# Sensor_IO_Buttons_LED.net
KiCad netlist of a schematic drawn in Altium Designer
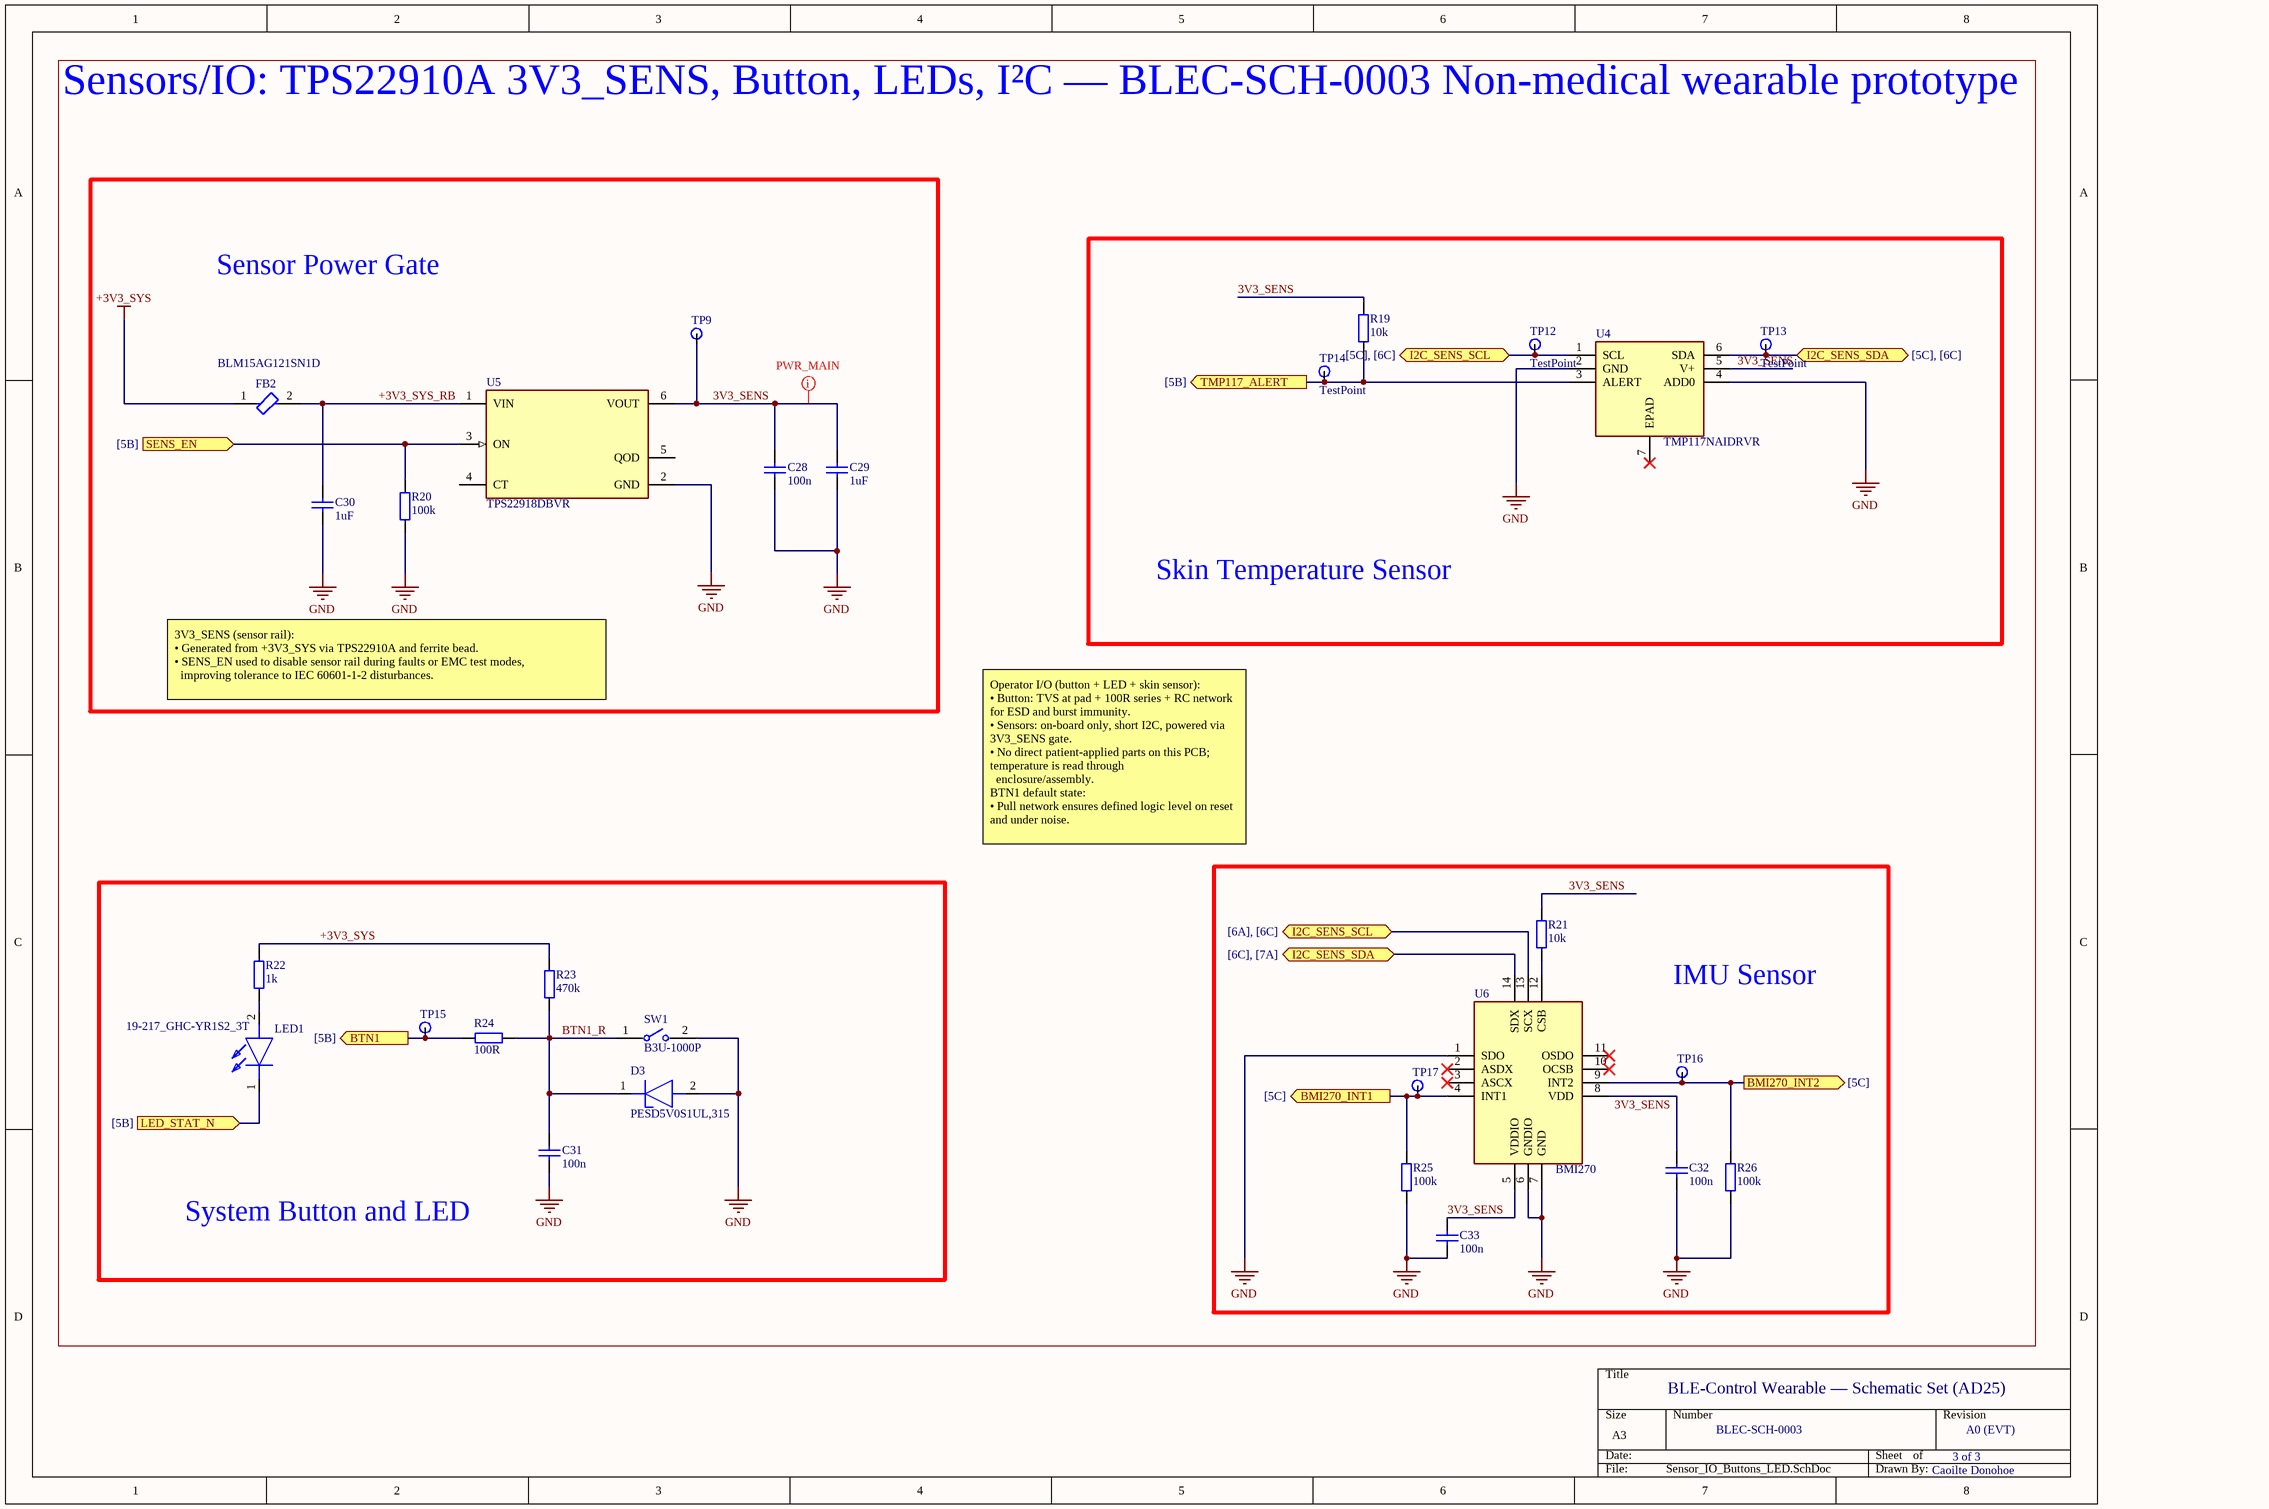
[diagram p0: Sensor_IO_Buttons_LED.SchDoc]

(export (version "E")
  (design (tool "Eeschema 10.0.6"))
  (components
    (comp (ref "C28")
      (value "100n")
      (footprint "CAP_0402")
      (description "Ceramic Chip Capacitor 0402")
      (fields (field (name "VOLTAGE") "10V") (field (name "TOLERANCE") "10%"))
      (libsource (lib "BLE-Control") (part "C_0402"))
    )
    (comp (ref "C29")
      (value "1uF")
      (footprint "CAP_0402")
      (description "Ceramic Chip Capacitor 0402")
      (fields (field (name "VOLTAGE") "10V") (field (name "TOLERANCE") "10%"))
      (libsource (lib "BLE-Control") (part "C_0402"))
    )
    (comp (ref "C30")
      (value "1uF")
      (footprint "CAP_0402")
      (description "Ceramic Chip Capacitor 0402")
      (fields (field (name "VOLTAGE") "10V") (field (name "TOLERANCE") "10%"))
      (libsource (lib "BLE-Control") (part "C_0402"))
    )
    (comp (ref "C31")
      (value "100n")
      (footprint "CAP_0402")
      (description "Ceramic Chip Capacitor 0402")
      (fields (field (name "VOLTAGE") "10V") (field (name "TOLERANCE") "10%"))
      (libsource (lib "BLE-Control") (part "C_0402"))
    )
    (comp (ref "C32")
      (value "100n")
      (footprint "CAP_0402")
      (description "Ceramic Chip Capacitor 0402")
      (fields (field (name "VOLTAGE") "10V") (field (name "TOLERANCE") "10%"))
      (libsource (lib "BLE-Control") (part "C_0402"))
    )
    (comp (ref "C33")
      (value "100n")
      (footprint "CAP_0402")
      (description "Ceramic Chip Capacitor 0402")
      (fields (field (name "VOLTAGE") "10V") (field (name "TOLERANCE") "10%"))
      (libsource (lib "BLE-Control") (part "C_0402"))
    )
    (comp (ref "D3")
      (value "PESD5V0S1UL,315")
      (footprint "SamacSys:PESD5V0S1BL315")
      (description "Diode ESD (Uni-directional)")
      (fields (field (name "MOUSER PART NUMBER") "771-PESD5V0S1UL315"))
      (libsource (lib "BLE-Control") (part "PESD5V0S1UL,315"))
    )
    (comp (ref "FB2")
      (value "BLM15AG121SN1D")
      (footprint "FP-BLM15-0_05-IPC_A")
      (description "Chip Ferrite Bead, 0402, 120Ω @ 100MHz, 0.19Ω, 25%, 550mA")
      (fields (field (name "TOLERANCE") "25%"))
      (libsource (lib "BLE-Control") (part "CMP-0686-00170-4"))
    )
    (comp (ref "LED1")
      (value "19-217_GHC-YR1S2_3T")
      (footprint "SamacSys:LEDC1608X50N")
      (description "LED")
      (fields
        (field (name "MANUFACTURER_PART_NUMBER") "19-217/GHC-YR1S2/3T")
        (field (name "MOUSER PART NUMBER") "638-19217GHCYR1S23T")
      )
      (libsource (lib "BLE-Control") (part "19-217_GHC-YR1S2_3T"))
    )
    (comp (ref "R19")
      (value "10k")
      (footprint "RES_0402")
      (description "Resistor SMD 0402")
      (libsource (lib "BLE-Control") (part "R_0402"))
    )
    (comp (ref "R20")
      (value "100k")
      (footprint "BLE-Control:RES_0402")
      (description "Resistor SMD 0402")
      (libsource (lib "BLE-Control") (part "R_0402"))
    )
    (comp (ref "R21")
      (value "10k")
      (footprint "RES_0402")
      (description "Resistor SMD 0402")
      (libsource (lib "BLE-Control") (part "R_0402"))
    )
    (comp (ref "R22")
      (value "1k")
      (footprint "RES_0402")
      (description "Resistor SMD 0402")
      (libsource (lib "BLE-Control") (part "R_0402"))
    )
    (comp (ref "R23")
      (value "470k")
      (footprint "RES_0402")
      (description "Resistor SMD 0402")
      (libsource (lib "BLE-Control") (part "R_0402"))
    )
    (comp (ref "R24")
      (value "100R")
      (footprint "RES_0402")
      (description "Resistor SMD 0402")
      (libsource (lib "BLE-Control") (part "R_0402"))
    )
    (comp (ref "R25")
      (value "100k")
      (footprint "RES_0402")
      (description "Resistor SMD 0402")
      (libsource (lib "BLE-Control") (part "R_0402"))
    )
    (comp (ref "R26")
      (value "100k")
      (footprint "RES_0402")
      (description "Resistor SMD 0402")
      (libsource (lib "BLE-Control") (part "R_0402"))
    )
    (comp (ref "SW1")
      (value "B3U-1000P")
      (footprint "FP-B3U-1000P-MFG")
      (description "SWITCH TACTILE SPST-NO 0.05A 12V")
      (libsource (lib "BLE-Control") (part "Omron B3U-1000P_Switch"))
    )
    (comp (ref "TP9")
      (value "~")
      (footprint "TP_VIA_0p75")
      (libsource (lib "BLE-Control") (part "TestPoint"))
    )
    (comp (ref "TP12")
      (value "TestPoint")
      (footprint "TP_VIA_0p75")
      (libsource (lib "BLE-Control") (part "TestPoint"))
    )
    (comp (ref "TP13")
      (value "TestPoint")
      (footprint "TP_VIA_0p75")
      (libsource (lib "BLE-Control") (part "TestPoint"))
    )
    (comp (ref "TP14")
      (value "TestPoint")
      (footprint "TP_VIA_0p75")
      (libsource (lib "BLE-Control") (part "TestPoint"))
    )
    (comp (ref "TP15")
      (value "~")
      (footprint "TP_VIA_0p75")
      (libsource (lib "BLE-Control") (part "TestPoint"))
    )
    (comp (ref "TP16")
      (value "~")
      (footprint "TP_VIA_0p75")
      (libsource (lib "BLE-Control") (part "TestPoint"))
    )
    (comp (ref "TP17")
      (value "~")
      (footprint "TP_VIA_0p75")
      (libsource (lib "BLE-Control") (part "TestPoint"))
    )
    (comp (ref "U4")
      (value "TMP117NAIDRVR")
      (footprint "SON65P200X200X80-7N")
      (description "Integrated Circuit")
      (fields (field (name "MOUSER PART NUMBER") "595-TMP117NAIDRVR"))
      (libsource (lib "*") (part "TMP117NAIDRVR"))
    )
    (comp (ref "U5")
      (value "TPS22918DBVR")
      (footprint "FP-DBV0006A-IPC_B")
      (description "IC SINGLE CHANNEL LOAD SWITCH")
      (libsource (lib "BLE-Control") (part "TPS22918DBVR"))
    )
    (comp (ref "U6")
      (value "BMI270")
      (footprint "BMI270")
      (description "Integrated Circuit")
      (fields (field (name "MOUSER PART NUMBER") "262-BMI270"))
      (libsource (lib "*") (part "BMI270"))
    )
  )
  (nets
    (net (code "1") (name "+3V3_SYS") (class "Default")
      (node (ref "FB2") (pin "1") (pinfunction "1_1") (pintype "passive"))
      (node (ref "R22") (pin "2") (pinfunction "2_2") (pintype "passive"))
      (node (ref "R23") (pin "2") (pinfunction "2_2") (pintype "passive"))
    )
    (net (code "2") (name "/+3V3_SYS_RB") (class "Default")
      (node (ref "C30") (pin "2") (pinfunction "2_2") (pintype "passive"))
      (node (ref "FB2") (pin "2") (pinfunction "2_2") (pintype "passive"))
      (node (ref "U5") (pin "1") (pinfunction "VIN_1") (pintype "power_in"))
    )
    (net (code "3") (name "/3V3_SENS") (class "Default")
      (node (ref "C28") (pin "2") (pinfunction "2_2") (pintype "passive"))
      (node (ref "C29") (pin "2") (pinfunction "2_2") (pintype "passive"))
      (node (ref "C32") (pin "2") (pinfunction "2_2") (pintype "passive"))
      (node (ref "C33") (pin "2") (pinfunction "2_2") (pintype "passive"))
      (node (ref "R19") (pin "2") (pinfunction "2_2") (pintype "passive"))
      (node (ref "R21") (pin "2") (pinfunction "2_2") (pintype "passive"))
      (node (ref "TP9") (pin "1") (pinfunction "0_1") (pintype "passive"))
      (node (ref "U4") (pin "5") (pinfunction "V+_5") (pintype "passive"))
      (node (ref "U5") (pin "6") (pinfunction "VOUT_6") (pintype "passive"))
      (node (ref "U6") (pin "5") (pinfunction "VDDIO_5") (pintype "passive"))
      (node (ref "U6") (pin "8") (pinfunction "VDD_8") (pintype "passive"))
    )
    (net (code "4") (name "/BMI270_INT1") (class "Default")
      (node (ref "R25") (pin "2") (pinfunction "2_2") (pintype "passive"))
      (node (ref "TP17") (pin "1") (pinfunction "0_1") (pintype "passive"))
      (node (ref "U6") (pin "4") (pinfunction "INT1_4") (pintype "passive"))
    )
    (net (code "5") (name "/BMI270_INT2") (class "Default")
      (node (ref "R26") (pin "2") (pinfunction "2_2") (pintype "passive"))
      (node (ref "TP16") (pin "1") (pinfunction "0_1") (pintype "passive"))
      (node (ref "U6") (pin "9") (pinfunction "INT2_9") (pintype "passive"))
    )
    (net (code "6") (name "/BTN1") (class "Default")
      (node (ref "R24") (pin "2") (pinfunction "2_2") (pintype "passive"))
      (node (ref "TP15") (pin "1") (pinfunction "0_1") (pintype "passive"))
    )
    (net (code "7") (name "/BTN1_R") (class "Default")
      (node (ref "C31") (pin "2") (pinfunction "2_2") (pintype "passive"))
      (node (ref "D3") (pin "1") (pinfunction "K_1") (pintype "passive"))
      (node (ref "R23") (pin "1") (pinfunction "1_1") (pintype "passive"))
      (node (ref "R24") (pin "1") (pinfunction "1_1") (pintype "passive"))
      (node (ref "SW1") (pin "1") (pinfunction "1_1") (pintype "passive"))
    )
    (net (code "8") (name "/I2C_SENS_SCL") (class "Default")
      (node (ref "TP12") (pin "1") (pinfunction "0_1") (pintype "passive"))
      (node (ref "U4") (pin "1") (pinfunction "SCL_1") (pintype "passive"))
      (node (ref "U6") (pin "13") (pinfunction "SCX_13") (pintype "passive"))
    )
    (net (code "9") (name "/I2C_SENS_SDA") (class "Default")
      (node (ref "TP13") (pin "1") (pinfunction "0_1") (pintype "passive"))
      (node (ref "U4") (pin "6") (pinfunction "SDA_6") (pintype "passive"))
      (node (ref "U6") (pin "14") (pinfunction "SDX_14") (pintype "passive"))
    )
    (net (code "10") (name "/LED_STAT_N") (class "Default")
      (node (ref "LED1") (pin "1") (pinfunction "K_1") (pintype "passive"))
    )
    (net (code "11") (name "/SENS_EN") (class "Default")
      (node (ref "R20") (pin "2") (pinfunction "2_2") (pintype "passive"))
      (node (ref "U5") (pin "3") (pinfunction "ON_3") (pintype "input"))
    )
    (net (code "12") (name "/TMP117_ALERT") (class "Default")
      (node (ref "R19") (pin "1") (pinfunction "1_1") (pintype "passive"))
      (node (ref "TP14") (pin "1") (pinfunction "0_1") (pintype "passive"))
      (node (ref "U4") (pin "3") (pinfunction "ALERT_3") (pintype "passive"))
    )
    (net (code "13") (name "GND") (class "Default")
      (node (ref "C28") (pin "1") (pinfunction "1_1") (pintype "passive"))
      (node (ref "C29") (pin "1") (pinfunction "1_1") (pintype "passive"))
      (node (ref "C30") (pin "1") (pinfunction "1_1") (pintype "passive"))
      (node (ref "C31") (pin "1") (pinfunction "1_1") (pintype "passive"))
      (node (ref "C32") (pin "1") (pinfunction "1_1") (pintype "passive"))
      (node (ref "C33") (pin "1") (pinfunction "1_1") (pintype "passive"))
      (node (ref "D3") (pin "2") (pinfunction "A_2") (pintype "passive"))
      (node (ref "R20") (pin "1") (pinfunction "1_1") (pintype "passive"))
      (node (ref "R25") (pin "1") (pinfunction "1_1") (pintype "passive"))
      (node (ref "R26") (pin "1") (pinfunction "1_1") (pintype "passive"))
      (node (ref "SW1") (pin "2") (pinfunction "2_2") (pintype "passive"))
      (node (ref "U4") (pin "2") (pinfunction "GND_2") (pintype "passive"))
      (node (ref "U4") (pin "4") (pinfunction "ADD0_4") (pintype "passive"))
      (node (ref "U5") (pin "2") (pinfunction "GND_2") (pintype "power_in"))
      (node (ref "U6") (pin "1") (pinfunction "SDO_1") (pintype "passive"))
      (node (ref "U6") (pin "6") (pinfunction "GNDIO_6") (pintype "passive"))
      (node (ref "U6") (pin "7") (pinfunction "GND_7") (pintype "passive"))
    )
    (net (code "14") (name "Net-(LED1-A)") (class "Default")
      (node (ref "LED1") (pin "2") (pinfunction "A_2") (pintype "passive"))
      (node (ref "R22") (pin "1") (pinfunction "1_1") (pintype "passive"))
    )
    (net (code "15") (name "Net-(U6-CSB)") (class "Default")
      (node (ref "R21") (pin "1") (pinfunction "1_1") (pintype "passive"))
      (node (ref "U6") (pin "12") (pinfunction "CSB_12") (pintype "passive"))
    )
    (net (code "16") (name "unconnected-(U4-EPAD-Pad7)") (class "Default")
      (node (ref "U4") (pin "7") (pinfunction "EPAD_7") (pintype "passive+no_connect"))
    )
    (net (code "17") (name "unconnected-(U5-CT-Pad4)") (class "Default")
      (node (ref "U5") (pin "4") (pinfunction "CT_4") (pintype "passive"))
    )
    (net (code "18") (name "unconnected-(U5-QOD-Pad5)") (class "Default")
      (node (ref "U5") (pin "5") (pinfunction "QOD_5") (pintype "passive"))
    )
    (net (code "19") (name "unconnected-(U6-ASCX-Pad3)") (class "Default")
      (node (ref "U6") (pin "3") (pinfunction "ASCX_3") (pintype "passive+no_connect"))
    )
    (net (code "20") (name "unconnected-(U6-ASDX-Pad2)") (class "Default")
      (node (ref "U6") (pin "2") (pinfunction "ASDX_2") (pintype "passive+no_connect"))
    )
    (net (code "21") (name "unconnected-(U6-OCSB-Pad10)") (class "Default")
      (node (ref "U6") (pin "10") (pinfunction "OCSB_10") (pintype "passive+no_connect"))
    )
    (net (code "22") (name "unconnected-(U6-OSDO-Pad11)") (class "Default")
      (node (ref "U6") (pin "11") (pinfunction "OSDO_11") (pintype "passive+no_connect"))
    )
  )
)
